# C210_0005_NINA_Module_220601.net
KiCad netlist of a schematic drawn in Altium Designer
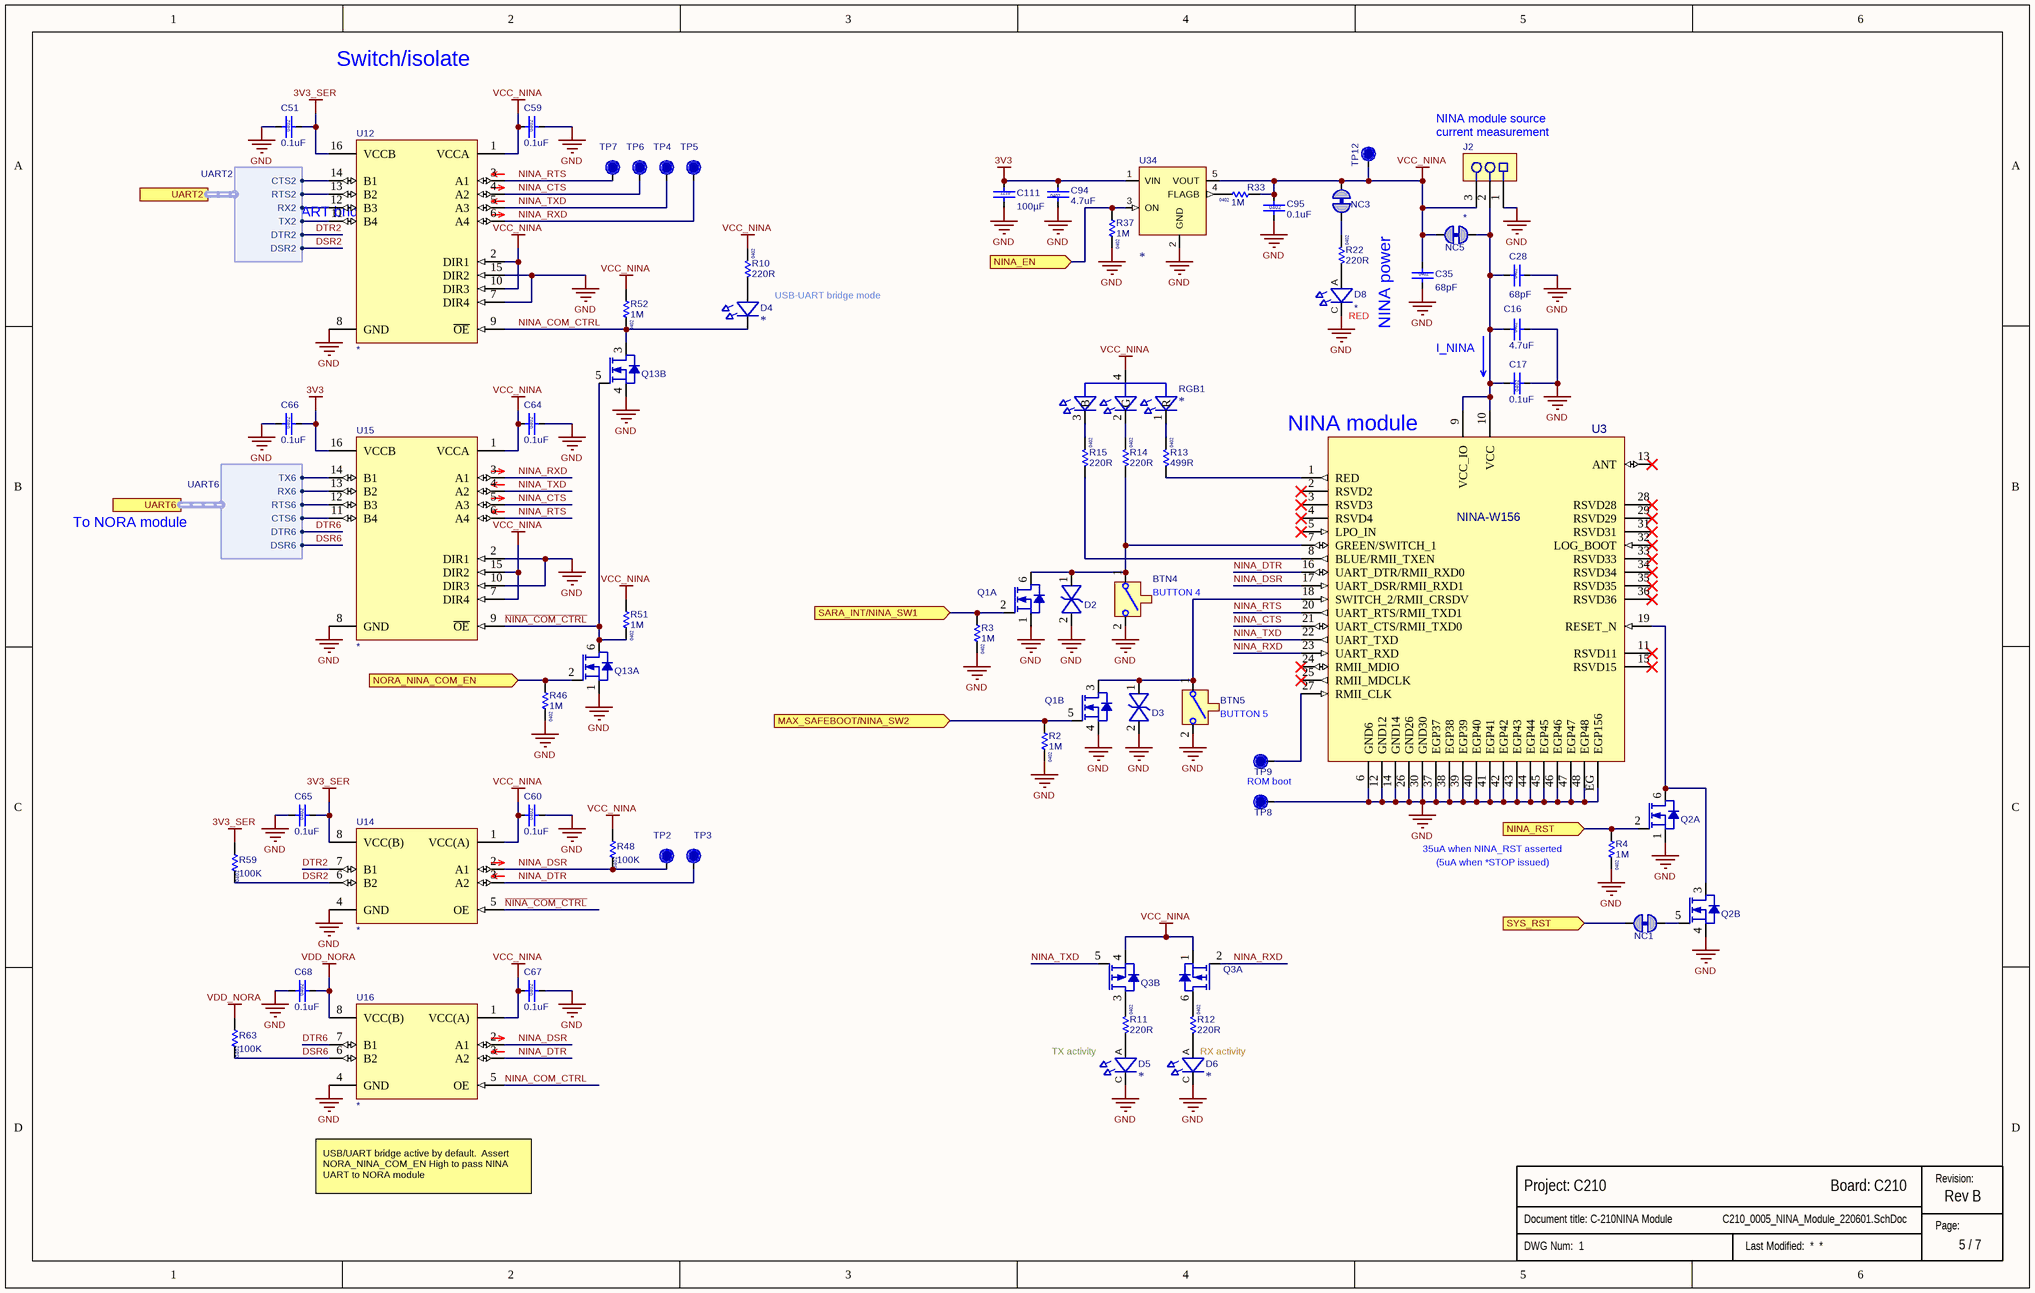
[diagram p0: C210_0005_NINA_Module_220601.SchDoc]

(export (version "E")
  (design (tool "Eeschema 10.0.6"))
  (components
    (comp (ref "BTN4")
      (value "135-00007")
      (footprint "B3U-1000P")
      (description "Button, Momentary SPST-NO, 0.05A, 12V, 3mm x 2.5mm")
      (fields (field (name "VOLTAGE") "12VDC"))
      (libsource (lib "Arena_Parts_DB_Lib") (part "SW_SPST"))
    )
    (comp (ref "BTN5")
      (value "135-00007")
      (footprint "B3U-1000P")
      (description "Button, Momentary SPST-NO, 0.05A, 12V, 3mm x 2.5mm")
      (fields (field (name "VOLTAGE") "12VDC"))
      (libsource (lib "Arena_Parts_DB_Lib") (part "SW_SPST"))
    )
    (comp (ref "C16")
      (value "4.7uF")
      (footprint "Cap 0402 HD")
      (description "Cap, Ceramic 4.7uF 10V 20% X5R 0402")
      (fields
        (field (name "SIZE") "0402")
        (field (name "PART NUMBER") "120-00020")
        (field (name "TOLERANCE") "+/- 20%")
      )
      (libsource (lib "Arena_Parts_DB_Lib") (part "Cap Chip"))
    )
    (comp (ref "C17")
      (value "0.1uF")
      (footprint "Cap 0402 HD")
      (description "Cap, Ceramic 0.1uF 10V 10% X5R 0402")
      (fields
        (field (name "SIZE") "0402")
        (field (name "PART NUMBER") "120-00016")
        (field (name "MANUFACTURER") "Murata Electronics North America")
      )
      (libsource (lib "Arena_Parts_DB_Lib") (part "Cap Chip"))
    )
    (comp (ref "C28")
      (value "68pF")
      (footprint "Cap 0402 HD")
      (description "Cap, Ceramic, 68pF, 50V, 1%, NP0, 0402")
      (fields
        (field (name "SIZE") "0402")
        (field (name "PART NUMBER") "120-00047")
        (field (name "TOLERANCE") "+/- 1%")
      )
      (libsource (lib "Arena_Parts_DB_Lib") (part "Cap Chip"))
    )
    (comp (ref "C35")
      (value "68pF")
      (footprint "Cap 0402 HD")
      (description "Cap, Ceramic, 68pF, 50V, 1%, NP0, 0402")
      (fields
        (field (name "SIZE") "0402")
        (field (name "PART NUMBER") "120-00047")
        (field (name "TOLERANCE") "+/- 1%")
      )
      (libsource (lib "Arena_Parts_DB_Lib") (part "Cap Chip"))
    )
    (comp (ref "C51")
      (value "0.1uF")
      (footprint "Cap 0402 HD")
      (description "Cap, Ceramic 0.1uF 10V 10% X5R 0402")
      (fields
        (field (name "SIZE") "0402")
        (field (name "PART NUMBER") "120-00016")
        (field (name "MANUFACTURER") "Murata Electronics North America")
      )
      (libsource (lib "Arena_Parts_DB_Lib") (part "Cap Chip"))
    )
    (comp (ref "C59")
      (value "0.1uF")
      (footprint "Cap 0402 HD")
      (description "Cap, Ceramic 0.1uF 10V 10% X5R 0402")
      (fields
        (field (name "SIZE") "0402")
        (field (name "PART NUMBER") "120-00016")
        (field (name "MANUFACTURER") "Murata Electronics North America")
      )
      (libsource (lib "Arena_Parts_DB_Lib") (part "Cap Chip"))
    )
    (comp (ref "C60")
      (value "0.1uF")
      (footprint "Cap 0402 HD")
      (description "Cap, Ceramic 0.1uF 10V 10% X5R 0402")
      (fields
        (field (name "SIZE") "0402")
        (field (name "PART NUMBER") "120-00016")
        (field (name "MANUFACTURER") "Murata Electronics North America")
      )
      (libsource (lib "Arena_Parts_DB_Lib") (part "Cap Chip"))
    )
    (comp (ref "C64")
      (value "0.1uF")
      (footprint "Cap 0402 HD")
      (description "Cap, Ceramic 0.1uF 10V 10% X5R 0402")
      (fields
        (field (name "SIZE") "0402")
        (field (name "PART NUMBER") "120-00016")
        (field (name "MANUFACTURER") "Murata Electronics North America")
      )
      (libsource (lib "Arena_Parts_DB_Lib") (part "Cap Chip"))
    )
    (comp (ref "C65")
      (value "0.1uF")
      (footprint "Cap 0402 HD")
      (description "Cap, Ceramic 0.1uF 10V 10% X5R 0402")
      (fields
        (field (name "SIZE") "0402")
        (field (name "PART NUMBER") "120-00016")
        (field (name "MANUFACTURER") "Murata Electronics North America")
      )
      (libsource (lib "Arena_Parts_DB_Lib") (part "Cap Chip"))
    )
    (comp (ref "C66")
      (value "0.1uF")
      (footprint "Cap 0402 HD")
      (description "Cap, Ceramic 0.1uF 10V 10% X5R 0402")
      (fields
        (field (name "SIZE") "0402")
        (field (name "PART NUMBER") "120-00016")
        (field (name "MANUFACTURER") "Murata Electronics North America")
      )
      (libsource (lib "Arena_Parts_DB_Lib") (part "Cap Chip"))
    )
    (comp (ref "C67")
      (value "0.1uF")
      (footprint "Cap 0402 HD")
      (description "Cap, Ceramic 0.1uF 10V 10% X5R 0402")
      (fields
        (field (name "SIZE") "0402")
        (field (name "PART NUMBER") "120-00016")
        (field (name "MANUFACTURER") "Murata Electronics North America")
      )
      (libsource (lib "Arena_Parts_DB_Lib") (part "Cap Chip"))
    )
    (comp (ref "C68")
      (value "0.1uF")
      (footprint "Cap 0402 HD")
      (description "Cap, Ceramic 0.1uF 10V 10% X5R 0402")
      (fields
        (field (name "SIZE") "0402")
        (field (name "PART NUMBER") "120-00016")
        (field (name "MANUFACTURER") "Murata Electronics North America")
      )
      (libsource (lib "Arena_Parts_DB_Lib") (part "Cap Chip"))
    )
    (comp (ref "C94")
      (value "4.7uF")
      (footprint "Cap 0402 HD")
      (description "Cap, Ceramic 4.7uF 10V 20% X5R 0402")
      (fields
        (field (name "SIZE") "0402")
        (field (name "PART NUMBER") "120-00020")
        (field (name "TOLERANCE") "+/- 20%")
      )
      (libsource (lib "Arena_Parts_DB_Lib") (part "Cap Chip"))
    )
    (comp (ref "C95")
      (value "0.1uF")
      (footprint "Cap 0402 HD")
      (description "Cap, Ceramic 0.1uF 10V 10% X5R 0402")
      (fields
        (field (name "SIZE") "0402")
        (field (name "PART NUMBER") "120-00016")
        (field (name "MANUFACTURER") "Murata Electronics North America")
      )
      (libsource (lib "Arena_Parts_DB_Lib") (part "Cap Chip"))
    )
    (comp (ref "C111")
      (value "100µF")
      (footprint "Cap 1210")
      (description "100µF ±20% 10V Ceramic Capacitor X5R 1210 (3225 Metric)")
      (fields
        (field (name "SIZE") "1210")
        (field (name "PART NUMBER") "120-00223")
        (field (name "TOLERANCE") "+/- 20%")
      )
      (libsource (lib "Arena_Parts_DB_Lib") (part "Cap Chip"))
    )
    (comp (ref "D2")
      (value "110-00041")
      (footprint "SOD-523_ALT")
      (description "Diode TVS 5VWM BiDIR SOD523")
      (fields (field (name "VOLTAGE") "5VWM"))
      (libsource (lib "Arena_Parts_DB_Lib") (part "Diode_TVS"))
    )
    (comp (ref "D3")
      (value "110-00041")
      (footprint "SOD-523_ALT")
      (description "Diode TVS 5VWM BiDIR SOD523")
      (fields (field (name "VOLTAGE") "5VWM"))
      (libsource (lib "Arena_Parts_DB_Lib") (part "Diode_TVS"))
    )
    (comp (ref "D4")
      (value "115-00023")
      (footprint "LED-0603")
      (description "LED BLUE DIFFUSED 0603 SMD")
      (fields (field (name "COLOR") "*") (field (name "VOLTAGE") "None"))
      (libsource (lib "Arena_Parts_DB_Lib") (part "LED_BASE"))
    )
    (comp (ref "D5")
      (value "115-00019")
      (footprint "LTST-C190KGKT")
      (description "DIODE, LED, SMT, GREEN, CLEAR LENS, 2.0V 20mA, 0603")
      (fields (field (name "VOLTAGE") "2.0V") (field (name "COLOR") "*"))
      (libsource (lib "LTST-C190KGKT") (part "LTST-C190KGKT"))
    )
    (comp (ref "D6")
      (value "LTST-C190YKT")
      (footprint "LTST-C190YKT")
      (description "DIODE, LED, SMT, YELLOW, CLEAR LENS, 2.1V 10mA, 0603")
      (fields (field (name "VOLTAGE") "2.1V") (field (name "COLOR") "*"))
      (libsource (lib "LTST-C190YKT") (part "LTST-C190YKT"))
    )
    (comp (ref "D8")
      (value "LTST-C190EKT")
      (footprint "LTST-C190EKT")
      (description "DIODE, LED, SMT, Red, CLEAR LENS, 2.0V 10mA, 0603")
      (fields (field (name "VOLTAGE") "2.0V") (field (name "COLOR") "*"))
      (libsource (lib "LTST-C190EKT") (part "LTST-C190EKT"))
    )
    (comp (ref "J2")
      (value "130-00105")
      (footprint "HDR-0.1P-3Pin-1Row-SMT")
      (description "Header, 0.100\" Pitch, 3 Pin, Vertical SMT, Black")
      (fields (field (name "MANUFACTURER P/N") "*") (field (name "VOLTAGE") "None"))
      (libsource (lib "Arena_Parts_DB_Lib") (part "CON-3Pin_1Row"))
    )
    (comp (ref "NC1")
      (value "Solderbridge-ShortDNP")
      (footprint "Solderbridge-Short")
      (description "Solderbridge-Short")
      (fields (field (name "ADDED BY") "Paul B"))
      (libsource (lib "") (part "Solderbridge-Short_1"))
    )
    (comp (ref "NC3")
      (value "Solderbridge-ShortDNP")
      (footprint "Solderbridge-Short")
      (description "Solderbridge-Short")
      (fields (field (name "ADDED BY") "Paul B"))
      (libsource (lib "PCB_Misc") (part "Solderbridge-Short"))
    )
    (comp (ref "NC5")
      (value "Solderbridge-ShortDNP")
      (footprint "Solderbridge-Short")
      (description "Solderbridge-Short")
      (fields (field (name "ADDED BY") "Paul B"))
      (libsource (lib "") (part "Solderbridge-Short_1"))
    )
    (comp (ref "Q1")
      (value "140-00016")
      (footprint "SOT-563")
      (description "MOSFET 2N-CH 20V 0.8A, SOT-563")
      (fields (field (name "VOLTAGE") "20V"))
      (libsource (lib "Arena_Parts_DB_Lib") (part "MOSFET-N-Dual"))
    )
    (comp (ref "Q2")
      (value "140-00016")
      (footprint "SOT-563")
      (description "MOSFET 2N-CH 20V 0.8A, SOT-563")
      (fields (field (name "VOLTAGE") "20V"))
      (libsource (lib "Arena_Parts_DB_Lib") (part "MOSFET-N-Dual"))
    )
    (comp (ref "Q3")
      (value "FDY2000PZ")
      (footprint "FDY2000PZ")
      (description "MOSFET DUAL P-CH 20V SOT-563, -350mA")
      (fields (field (name "VOLTAGE") "20V"))
      (libsource (lib "FDY2000PZ") (part "MOSFET-Dual-P_Chan"))
    )
    (comp (ref "Q13")
      (value "140-00016")
      (footprint "SOT-563")
      (description "MOSFET 2N-CH 20V 0.8A, SOT-563")
      (fields (field (name "VOLTAGE") "20V"))
      (libsource (lib "Arena_Parts_DB_Lib") (part "MOSFET-N-Dual"))
    )
    (comp (ref "R2")
      (value "1M")
      (footprint "RES 0402 HD")
      (description "Resistor 1M ohm 1%, 1/16W, 0402")
      (fields
        (field (name "SIZE") "0402")
        (field (name "PART NUMBER") "180-00054")
        (field (name "POWER") "1/16W")
      )
      (libsource (lib "Arena_Parts_DB_Lib") (part "Res sm"))
    )
    (comp (ref "R3")
      (value "1M")
      (footprint "RES 0402 HD")
      (description "Resistor 1M ohm 1%, 1/16W, 0402")
      (fields
        (field (name "SIZE") "0402")
        (field (name "PART NUMBER") "180-00054")
        (field (name "POWER") "1/16W")
      )
      (libsource (lib "Arena_Parts_DB_Lib") (part "Res sm"))
    )
    (comp (ref "R4")
      (value "1M")
      (footprint "RES 0402 HD")
      (description "Resistor 1M ohm 1%, 1/16W, 0402")
      (fields
        (field (name "SIZE") "0402")
        (field (name "PART NUMBER") "180-00054")
        (field (name "POWER") "1/16W")
      )
      (libsource (lib "Arena_Parts_DB_Lib") (part "Res sm"))
    )
    (comp (ref "R10")
      (value "220R")
      (footprint "RES 0402 HD")
      (description "Resistor, 220ohm, 5%, 1/16W, 0402.")
      (fields
        (field (name "SIZE") "0402")
        (field (name "PART NUMBER") "180-00098")
        (field (name "MANUFACTURER") "Panasonic Electronic Components")
      )
      (libsource (lib "Arena_Parts_DB_Lib") (part "Res sm"))
    )
    (comp (ref "R11")
      (value "220R")
      (footprint "RES 0402 HD")
      (description "Resistor, 220ohm, 5%, 1/16W, 0402.")
      (fields
        (field (name "SIZE") "0402")
        (field (name "PART NUMBER") "180-00098")
        (field (name "MANUFACTURER") "Panasonic Electronic Components")
      )
      (libsource (lib "Arena_Parts_DB_Lib") (part "Res sm"))
    )
    (comp (ref "R12")
      (value "220R")
      (footprint "RES 0402 HD")
      (description "Resistor, 220ohm, 5%, 1/16W, 0402.")
      (fields
        (field (name "SIZE") "0402")
        (field (name "PART NUMBER") "180-00098")
        (field (name "MANUFACTURER") "Panasonic Electronic Components")
      )
      (libsource (lib "Arena_Parts_DB_Lib") (part "Res sm"))
    )
    (comp (ref "R13")
      (value "499R")
      (footprint "RES 0402 HD")
      (description "Resistor, 499ohm, 1%, 1/16W, 0402")
      (fields
        (field (name "SIZE") "0402")
        (field (name "PART NUMBER") "180-00031")
        (field (name "MANUFACTURER") "Rohm Semiconductor")
      )
      (libsource (lib "Arena_Parts_DB_Lib") (part "Res sm"))
    )
    (comp (ref "R14")
      (value "220R")
      (footprint "RES 0402 HD")
      (description "Resistor, 220ohm, 5%, 1/16W, 0402.")
      (fields
        (field (name "SIZE") "0402")
        (field (name "PART NUMBER") "180-00098")
        (field (name "MANUFACTURER") "Panasonic Electronic Components")
      )
      (libsource (lib "Arena_Parts_DB_Lib") (part "Res sm"))
    )
    (comp (ref "R15")
      (value "220R")
      (footprint "RES 0402 HD")
      (description "Resistor, 220ohm, 5%, 1/16W, 0402.")
      (fields
        (field (name "SIZE") "0402")
        (field (name "PART NUMBER") "180-00098")
        (field (name "MANUFACTURER") "Panasonic Electronic Components")
      )
      (libsource (lib "Arena_Parts_DB_Lib") (part "Res sm"))
    )
    (comp (ref "R22")
      (value "220R")
      (footprint "RES 0402 HD")
      (description "Resistor, 220ohm, 5%, 1/16W, 0402.")
      (fields
        (field (name "SIZE") "0402")
        (field (name "PART NUMBER") "180-00098")
        (field (name "MANUFACTURER") "Panasonic Electronic Components")
      )
      (libsource (lib "Arena_Parts_DB_Lib") (part "Res sm"))
    )
    (comp (ref "R33")
      (value "1M")
      (footprint "RES 0402 HD")
      (description "Resistor 1M ohm 1%, 1/16W, 0402")
      (fields
        (field (name "SIZE") "0402")
        (field (name "PART NUMBER") "180-00054")
        (field (name "POWER") "1/16W")
      )
      (libsource (lib "Arena_Parts_DB_Lib") (part "Res sm"))
    )
    (comp (ref "R37")
      (value "1M")
      (footprint "RES 0402 HD")
      (description "Resistor 1M ohm 1%, 1/16W, 0402")
      (fields
        (field (name "SIZE") "0402")
        (field (name "PART NUMBER") "180-00054")
        (field (name "POWER") "1/16W")
      )
      (libsource (lib "Arena_Parts_DB_Lib") (part "Res sm"))
    )
    (comp (ref "R46")
      (value "1M")
      (footprint "RES 0402 HD")
      (description "Resistor 1M ohm 1%, 1/16W, 0402")
      (fields
        (field (name "SIZE") "0402")
        (field (name "PART NUMBER") "180-00054")
        (field (name "POWER") "1/16W")
      )
      (libsource (lib "Arena_Parts_DB_Lib") (part "Res sm"))
    )
    (comp (ref "R48")
      (value "100K")
      (footprint "RES 0402 HD")
      (description "Resistor 100K ohm 1% 1/16W, 0402")
      (fields
        (field (name "SIZE") "0402")
        (field (name "PART NUMBER") "180-00093")
        (field (name "POWER") "1/16W")
      )
      (libsource (lib "Arena_Parts_DB_Lib") (part "Res sm"))
    )
    (comp (ref "R51")
      (value "1M")
      (footprint "RES 0402 HD")
      (description "Resistor 1M ohm 1%, 1/16W, 0402")
      (fields
        (field (name "SIZE") "0402")
        (field (name "PART NUMBER") "180-00054")
        (field (name "POWER") "1/16W")
      )
      (libsource (lib "Arena_Parts_DB_Lib") (part "Res sm"))
    )
    (comp (ref "R52")
      (value "1M")
      (footprint "RES 0402 HD")
      (description "Resistor 1M ohm 1%, 1/16W, 0402")
      (fields
        (field (name "SIZE") "0402")
        (field (name "PART NUMBER") "180-00054")
        (field (name "POWER") "1/16W")
      )
      (libsource (lib "Arena_Parts_DB_Lib") (part "Res sm"))
    )
    (comp (ref "R59")
      (value "100K")
      (footprint "RES 0402 HD")
      (description "Resistor 100K ohm 1% 1/16W, 0402")
      (fields
        (field (name "SIZE") "0402")
        (field (name "PART NUMBER") "180-00093")
        (field (name "POWER") "1/16W")
      )
      (libsource (lib "Arena_Parts_DB_Lib") (part "Res sm"))
    )
    (comp (ref "R63")
      (value "100K")
      (footprint "RES 0402 HD")
      (description "Resistor 100K ohm 1% 1/16W, 0402")
      (fields
        (field (name "SIZE") "0402")
        (field (name "PART NUMBER") "180-00093")
        (field (name "POWER") "1/16W")
      )
      (libsource (lib "Arena_Parts_DB_Lib") (part "Res sm"))
    )
    (comp (ref "RGB1")
      (value "115-00026")
      (footprint "LED_1616")
      (description "LED RGB SMT 0606")
      (fields (field (name "COLOR") "*") (field (name "VOLTAGE") "None"))
      (libsource (lib "Arena_Parts_DB_Lib") (part "LED_RGB_CA_4"))
    )
    (comp (ref "TP2")
      (value "TP")
      (footprint "TP12R")
      (description "Testpoint, Round 1.0mm Dia")
      (fields
        (field (name "PART NUMBER") "TP10R")
        (field (name "ADDED BY") "Jeremy D")
        (field (name "CHECKED BY") "Paul B")
      )
      (libsource (lib "PCB_Misc") (part "TP_R"))
    )
    (comp (ref "TP3")
      (value "TP")
      (footprint "TP12R")
      (description "Testpoint, Round 1.0mm Dia")
      (fields
        (field (name "PART NUMBER") "TP10R")
        (field (name "ADDED BY") "Jeremy D")
        (field (name "CHECKED BY") "Paul B")
      )
      (libsource (lib "PCB_Misc") (part "TP_R"))
    )
    (comp (ref "TP4")
      (value "TP")
      (footprint "TP12R")
      (description "Testpoint, Round 1.0mm Dia")
      (fields
        (field (name "PART NUMBER") "TP10R")
        (field (name "ADDED BY") "Jeremy D")
        (field (name "CHECKED BY") "Paul B")
      )
      (libsource (lib "PCB_Misc") (part "TP_R"))
    )
    (comp (ref "TP5")
      (value "TP")
      (footprint "TP12R")
      (description "Testpoint, Round 1.0mm Dia")
      (fields
        (field (name "PART NUMBER") "TP10R")
        (field (name "ADDED BY") "Jeremy D")
        (field (name "CHECKED BY") "Paul B")
      )
      (libsource (lib "PCB_Misc") (part "TP_R"))
    )
    (comp (ref "TP6")
      (value "TP")
      (footprint "TP12R")
      (description "Testpoint, Round 1.0mm Dia")
      (fields
        (field (name "PART NUMBER") "TP10R")
        (field (name "ADDED BY") "Jeremy D")
        (field (name "CHECKED BY") "Paul B")
      )
      (libsource (lib "PCB_Misc") (part "TP_R"))
    )
    (comp (ref "TP7")
      (value "TP")
      (footprint "TP12R")
      (description "Testpoint, Round 1.0mm Dia")
      (fields
        (field (name "PART NUMBER") "TP10R")
        (field (name "ADDED BY") "Jeremy D")
        (field (name "CHECKED BY") "Paul B")
      )
      (libsource (lib "PCB_Misc") (part "TP_R"))
    )
    (comp (ref "TP8")
      (value "TP")
      (footprint "TP12R")
      (description "Testpoint, Round 1.0mm Dia")
      (fields
        (field (name "PART NUMBER") "TP10R")
        (field (name "ADDED BY") "Jeremy D")
        (field (name "CHECKED BY") "Paul B")
      )
      (libsource (lib "PCB_Misc") (part "TP_R"))
    )
    (comp (ref "TP9")
      (value "TP")
      (footprint "TP12R")
      (description "Testpoint, Round 1.0mm Dia")
      (fields
        (field (name "PART NUMBER") "TP10R")
        (field (name "ADDED BY") "Jeremy D")
        (field (name "CHECKED BY") "Paul B")
      )
      (libsource (lib "PCB_Misc") (part "TP_R"))
    )
    (comp (ref "TP12")
      (value "TP")
      (footprint "TP12R")
      (description "Testpoint, Round 1.0mm Dia")
      (fields
        (field (name "PART NUMBER") "TP10R")
        (field (name "ADDED BY") "Jeremy D")
        (field (name "CHECKED BY") "Paul B")
      )
      (libsource (lib "PCB_Misc") (part "TP_R"))
    )
    (comp (ref "U3")
      (value "NINA-W156")
      (footprint "NINA_LGA48R_1400X1000X223_PCB")
      (description "u-blox NINA-W156 WiFi, Bluetooth dual-mode module")
      (fields (field (name "MANUFACTURER") "u-blox"))
      (libsource (lib "ubloxLib") (part "NINA-W156"))
    )
    (comp (ref "U12")
      (value "225-00011")
      (footprint "QFN0.5P2x6-16Pin_W-Pad")
      (description "Voltage Level Translator Bidirectional 1 Circuit 4 Channel 380Mbps 16-DHVQFN (2.5x3.5)")
      (fields (field (name "MANUFACTURER P/N") "*") (field (name "VOLTAGE") "3.6V"))
      (libsource (lib "Arena_Parts_DB_Lib") (part "74AVC4TD245"))
    )
    (comp (ref "U14")
      (value "225-00008")
      (footprint "QFN0.4P3x1-8Pin")
      (description "IC Dual Translating Transceiver, 8XQFN")
      (fields (field (name "MANUFACTURER P/N") "*") (field (name "VOLTAGE") "5.5V"))
      (libsource (lib "Arena_Parts_DB_Lib") (part "NTSX2102GU8H"))
    )
    (comp (ref "U15")
      (value "225-00011")
      (footprint "QFN0.5P2x6-16Pin_W-Pad")
      (description "Voltage Level Translator Bidirectional 1 Circuit 4 Channel 380Mbps 16-DHVQFN (2.5x3.5)")
      (fields (field (name "MANUFACTURER P/N") "*") (field (name "VOLTAGE") "3.6V"))
      (libsource (lib "Arena_Parts_DB_Lib") (part "74AVC4TD245"))
    )
    (comp (ref "U16")
      (value "225-00008")
      (footprint "QFN0.4P3x1-8Pin")
      (description "IC Dual Translating Transceiver, 8XQFN")
      (fields (field (name "MANUFACTURER P/N") "*") (field (name "VOLTAGE") "5.5V"))
      (libsource (lib "Arena_Parts_DB_Lib") (part "NTSX2102GU8H"))
    )
    (comp (ref "U34")
      (value "~")
      (footprint "SOT-23-5_2")
      (description "Load Switch, 400mA, 1.8-5.5V, Active High Enable, SOT-23-5")
      (fields (field (name "VOLTAGE") "5.5V") (field (name "MANUFACTURER P/N") "*"))
      (libsource (lib "FPF2104") (part "FPF2104"))
    )
  )
  (nets
    (net (code "3") (name "/CTS2") (class "Default")
      (node (ref "U12") (pin "14") (pinfunction "B1_14") (pintype "bidirectional"))
    )
    (net (code "4") (name "/CTS6") (class "Default")
      (node (ref "U15") (pin "11") (pinfunction "B4_11") (pintype "bidirectional"))
    )
    (net (code "5") (name "/DSR2") (class "Default")
      (node (ref "R59") (pin "2") (pinfunction "2_2") (pintype "passive"))
      (node (ref "U14") (pin "6") (pinfunction "B2_6") (pintype "bidirectional"))
    )
    (net (code "6") (name "/DSR6") (class "Default")
      (node (ref "R63") (pin "2") (pinfunction "2_2") (pintype "passive"))
      (node (ref "U16") (pin "6") (pinfunction "B2_6") (pintype "bidirectional"))
    )
    (net (code "7") (name "/DTR2") (class "Default")
      (node (ref "U14") (pin "7") (pinfunction "B1_7") (pintype "bidirectional"))
    )
    (net (code "8") (name "/DTR6") (class "Default")
      (node (ref "U16") (pin "7") (pinfunction "B1_7") (pintype "bidirectional"))
    )
    (net (code "9") (name "/MAX_SAFEBOOT{slash}NINA_SW2") (class "Default")
      (node (ref "Q1") (pin "5") (pinfunction "G2_5") (pintype "passive"))
      (node (ref "R2") (pin "1") (pinfunction "1_1") (pintype "passive"))
    )
    (net (code "10") (name "/NINA_COM_CTRL") (class "Default")
      (node (ref "D4") (pin "1") (pinfunction "C_1") (pintype "passive"))
      (node (ref "Q13") (pin "3") (pinfunction "D2_3") (pintype "passive"))
      (node (ref "R52") (pin "2") (pinfunction "2_2") (pintype "passive"))
      (node (ref "U12") (pin "9") (pinfunction "~{OE}_9") (pintype "input"))
      (node (ref "U16") (pin "5") (pinfunction "OE_5") (pintype "input"))
    )
    (net (code "11") (name "/NINA_CTS") (class "Default")
      (node (ref "TP6") (pin "1") (pintype "passive"))
      (node (ref "U12") (pin "4") (pinfunction "A2_4") (pintype "bidirectional"))
      (node (ref "U15") (pin "5") (pinfunction "A3_5") (pintype "bidirectional"))
      (node (ref "U3") (pin "21") (pinfunction "UART_CTS/RMII_TXD0_21") (pintype "bidirectional"))
    )
    (net (code "12") (name "/NINA_DSR") (class "Default")
      (node (ref "R48") (pin "2") (pinfunction "2_2") (pintype "passive"))
      (node (ref "TP2") (pin "1") (pintype "passive"))
      (node (ref "U14") (pin "2") (pinfunction "A1_2") (pintype "bidirectional"))
      (node (ref "U16") (pin "2") (pinfunction "A1_2") (pintype "bidirectional"))
      (node (ref "U3") (pin "17") (pinfunction "UART_DSR/RMII_RXD1_17") (pintype "input"))
    )
    (net (code "13") (name "/NINA_DTR") (class "Default")
      (node (ref "TP3") (pin "1") (pintype "passive"))
      (node (ref "U14") (pin "3") (pinfunction "A2_3") (pintype "bidirectional"))
      (node (ref "U16") (pin "3") (pinfunction "A2_3") (pintype "bidirectional"))
      (node (ref "U3") (pin "16") (pinfunction "UART_DTR/RMII_RXD0_16") (pintype "bidirectional"))
    )
    (net (code "14") (name "/NINA_EN") (class "Default")
      (node (ref "R37") (pin "1") (pinfunction "1_1") (pintype "passive"))
      (node (ref "U34") (pin "3") (pinfunction "ON_3") (pintype "input"))
    )
    (net (code "15") (name "/NINA_RST") (class "Default")
      (node (ref "Q2") (pin "2") (pinfunction "G1_2") (pintype "passive"))
      (node (ref "R4") (pin "1") (pinfunction "1_1") (pintype "passive"))
    )
    (net (code "16") (name "/NINA_RTS") (class "Default")
      (node (ref "TP7") (pin "1") (pintype "passive"))
      (node (ref "U12") (pin "3") (pinfunction "A1_3") (pintype "bidirectional"))
      (node (ref "U15") (pin "6") (pinfunction "A4_6") (pintype "bidirectional"))
      (node (ref "U3") (pin "20") (pinfunction "UART_RTS/RMII_TXD1_20") (pintype "output"))
    )
    (net (code "17") (name "/NINA_RXD") (class "Default")
      (node (ref "Q3") (pin "2") (pinfunction "G1_2") (pintype "passive"))
      (node (ref "TP5") (pin "1") (pintype "passive"))
      (node (ref "U12") (pin "6") (pinfunction "A4_6") (pintype "bidirectional"))
      (node (ref "U15") (pin "3") (pinfunction "A1_3") (pintype "bidirectional"))
      (node (ref "U3") (pin "23") (pinfunction "UART_RXD_23") (pintype "input"))
    )
    (net (code "18") (name "/NINA_TXD") (class "Default")
      (node (ref "Q3") (pin "5") (pinfunction "G2_5") (pintype "passive"))
      (node (ref "TP4") (pin "1") (pintype "passive"))
      (node (ref "U12") (pin "5") (pinfunction "A3_5") (pintype "bidirectional"))
      (node (ref "U15") (pin "4") (pinfunction "A2_4") (pintype "bidirectional"))
      (node (ref "U3") (pin "22") (pinfunction "UART_TXD_22") (pintype "output"))
    )
    (net (code "19") (name "/NORA_NINA_COM_EN") (class "Default")
      (node (ref "Q13") (pin "2") (pinfunction "G1_2") (pintype "passive"))
      (node (ref "R46") (pin "1") (pinfunction "1_1") (pintype "passive"))
    )
    (net (code "20") (name "/RTS2") (class "Default")
      (node (ref "U12") (pin "13") (pinfunction "B2_13") (pintype "bidirectional"))
    )
    (net (code "21") (name "/RTS6") (class "Default")
      (node (ref "U15") (pin "12") (pinfunction "B3_12") (pintype "bidirectional"))
    )
    (net (code "22") (name "/RX2") (class "Default")
      (node (ref "U12") (pin "12") (pinfunction "B3_12") (pintype "bidirectional"))
    )
    (net (code "23") (name "/RX6") (class "Default")
      (node (ref "U15") (pin "13") (pinfunction "B2_13") (pintype "bidirectional"))
    )
    (net (code "24") (name "/SARA_INT{slash}NINA_SW1") (class "Default")
      (node (ref "Q1") (pin "2") (pinfunction "G1_2") (pintype "passive"))
      (node (ref "R3") (pin "1") (pinfunction "1_1") (pintype "passive"))
    )
    (net (code "25") (name "/SYS_RST") (class "Default")
      (node (ref "NC1") (pin "2") (pinfunction "2_2") (pintype "passive"))
    )
    (net (code "26") (name "/TX2") (class "Default")
      (node (ref "U12") (pin "11") (pinfunction "B4_11") (pintype "bidirectional"))
    )
    (net (code "27") (name "/TX6") (class "Default")
      (node (ref "U15") (pin "14") (pinfunction "B1_14") (pintype "bidirectional"))
    )
    (net (code "30") (name "/~{NINA_COM_CTRL}") (class "Default")
      (node (ref "Q13") (pin "5") (pinfunction "G2_5") (pintype "passive"))
      (node (ref "Q13") (pin "6") (pinfunction "D1_6") (pintype "passive"))
      (node (ref "R51") (pin "2") (pinfunction "2_2") (pintype "passive"))
      (node (ref "U14") (pin "5") (pinfunction "OE_5") (pintype "input"))
      (node (ref "U15") (pin "9") (pinfunction "~{OE}_9") (pintype "input"))
    )
    (net (code "31") (name "3V3") (class "Default")
      (node (ref "C111") (pin "1") (pinfunction "1_1") (pintype "passive"))
      (node (ref "C66") (pin "2") (pinfunction "2_2") (pintype "passive"))
      (node (ref "C94") (pin "2") (pinfunction "2_2") (pintype "passive"))
      (node (ref "U15") (pin "16") (pinfunction "VCCB_16") (pintype "power_in"))
      (node (ref "U34") (pin "1") (pinfunction "VIN_1") (pintype "power_in"))
    )
    (net (code "32") (name "3V3_SER") (class "Default")
      (node (ref "C51") (pin "2") (pinfunction "2_2") (pintype "passive"))
      (node (ref "C65") (pin "2") (pinfunction "2_2") (pintype "passive"))
      (node (ref "R59") (pin "1") (pinfunction "1_1") (pintype "passive"))
      (node (ref "U12") (pin "16") (pinfunction "VCCB_16") (pintype "power_in"))
      (node (ref "U14") (pin "8") (pinfunction "VCC(B)_8") (pintype "power_in"))
    )
    (net (code "33") (name "GND") (class "Default")
      (node (ref "BTN4") (pin "2") (pinfunction "2_2") (pintype "passive"))
      (node (ref "BTN5") (pin "2") (pinfunction "2_2") (pintype "passive"))
      (node (ref "C111") (pin "2") (pinfunction "2_2") (pintype "passive"))
      (node (ref "C16") (pin "2") (pinfunction "2_2") (pintype "passive"))
      (node (ref "C17") (pin "1") (pinfunction "1_1") (pintype "passive"))
      (node (ref "C28") (pin "2") (pinfunction "2_2") (pintype "passive"))
      (node (ref "C35") (pin "2") (pinfunction "2_2") (pintype "passive"))
      (node (ref "C51") (pin "1") (pinfunction "1_1") (pintype "passive"))
      (node (ref "C59") (pin "2") (pinfunction "2_2") (pintype "passive"))
      (node (ref "C60") (pin "2") (pinfunction "2_2") (pintype "passive"))
      (node (ref "C64") (pin "2") (pinfunction "2_2") (pintype "passive"))
      (node (ref "C65") (pin "1") (pinfunction "1_1") (pintype "passive"))
      (node (ref "C66") (pin "1") (pinfunction "1_1") (pintype "passive"))
      (node (ref "C67") (pin "2") (pinfunction "2_2") (pintype "passive"))
      (node (ref "C68") (pin "1") (pinfunction "1_1") (pintype "passive"))
      (node (ref "C94") (pin "1") (pinfunction "1_1") (pintype "passive"))
      (node (ref "C95") (pin "2") (pinfunction "2_2") (pintype "passive"))
      (node (ref "D2") (pin "2") (pintype "passive"))
      (node (ref "D3") (pin "2") (pintype "passive"))
      (node (ref "D5") (pin "C") (pinfunction "Cathode_C") (pintype "passive"))
      (node (ref "D6") (pin "C") (pinfunction "Cathode_C") (pintype "passive"))
      (node (ref "D8") (pin "C") (pinfunction "Cathode_C") (pintype "passive"))
      (node (ref "J2") (pin "1") (pinfunction "1_1") (pintype "passive"))
      (node (ref "Q1") (pin "1") (pinfunction "S1_1") (pintype "passive"))
      (node (ref "Q1") (pin "4") (pinfunction "S2_4") (pintype "passive"))
      (node (ref "Q13") (pin "1") (pinfunction "S1_1") (pintype "passive"))
      (node (ref "Q13") (pin "4") (pinfunction "S2_4") (pintype "passive"))
      (node (ref "Q2") (pin "1") (pinfunction "S1_1") (pintype "passive"))
      (node (ref "Q2") (pin "4") (pinfunction "S2_4") (pintype "passive"))
      (node (ref "R2") (pin "2") (pinfunction "2_2") (pintype "passive"))
      (node (ref "R3") (pin "2") (pinfunction "2_2") (pintype "passive"))
      (node (ref "R37") (pin "2") (pinfunction "2_2") (pintype "passive"))
      (node (ref "R4") (pin "2") (pinfunction "2_2") (pintype "passive"))
      (node (ref "R46") (pin "2") (pinfunction "2_2") (pintype "passive"))
      (node (ref "TP8") (pin "1") (pintype "passive"))
      (node (ref "U12") (pin "15") (pinfunction "DIR2_15") (pintype "input"))
      (node (ref "U12") (pin "7") (pinfunction "DIR4_7") (pintype "input"))
      (node (ref "U12") (pin "8") (pinfunction "GND_8") (pintype "power_in"))
      (node (ref "U14") (pin "4") (pinfunction "GND_4") (pintype "power_in"))
      (node (ref "U15") (pin "10") (pinfunction "DIR3_10") (pintype "input"))
      (node (ref "U15") (pin "2") (pinfunction "DIR1_2") (pintype "input"))
      (node (ref "U15") (pin "8") (pinfunction "GND_8") (pintype "power_in"))
      (node (ref "U16") (pin "4") (pinfunction "GND_4") (pintype "power_in"))
      (node (ref "U3") (pin "12") (pinfunction "GND12_12") (pintype "power_in"))
      (node (ref "U3") (pin "14") (pinfunction "GND14_14") (pintype "power_in"))
      (node (ref "U3") (pin "26") (pinfunction "GND26_26") (pintype "power_in"))
      (node (ref "U3") (pin "30") (pinfunction "GND30_30") (pintype "power_in"))
      (node (ref "U3") (pin "37") (pinfunction "EGP37_37") (pintype "power_in"))
      (node (ref "U3") (pin "38") (pinfunction "EGP38_38") (pintype "power_in"))
      (node (ref "U3") (pin "39") (pinfunction "EGP39_39") (pintype "power_in"))
      (node (ref "U3") (pin "40") (pinfunction "EGP40_40") (pintype "power_in"))
      (node (ref "U3") (pin "41") (pinfunction "EGP41_41") (pintype "power_in"))
      (node (ref "U3") (pin "42") (pinfunction "EGP42_42") (pintype "power_in"))
      (node (ref "U3") (pin "43") (pinfunction "EGP43_43") (pintype "power_in"))
      (node (ref "U3") (pin "44") (pinfunction "EGP44_44") (pintype "power_in"))
      (node (ref "U3") (pin "45") (pinfunction "EGP45_45") (pintype "power_in"))
      (node (ref "U3") (pin "46") (pinfunction "EGP46_46") (pintype "power_in"))
      (node (ref "U3") (pin "47") (pinfunction "EGP47_47") (pintype "power_in"))
      (node (ref "U3") (pin "48") (pinfunction "EGP48_48") (pintype "power_in"))
      (node (ref "U3") (pin "6") (pinfunction "GND6_6") (pintype "power_in"))
      (node (ref "U3") (pin "EG") (pinfunction "EGP156_EG") (pintype "power_in"))
      (node (ref "U34") (pin "2") (pinfunction "GND_2") (pintype "power_in"))
    )
    (net (code "34") (name "Net-(D4-A)") (class "Default")
      (node (ref "D4") (pin "2") (pinfunction "A_2") (pintype "passive"))
      (node (ref "R10") (pin "1") (pinfunction "1_1") (pintype "passive"))
    )
    (net (code "35") (name "Net-(D5-Anode)") (class "Default")
      (node (ref "D5") (pin "A") (pinfunction "Anode_A") (pintype "passive"))
      (node (ref "R11") (pin "1") (pinfunction "1_1") (pintype "passive"))
    )
    (net (code "36") (name "Net-(D6-Anode)") (class "Default")
      (node (ref "D6") (pin "A") (pinfunction "Anode_A") (pintype "passive"))
      (node (ref "R12") (pin "1") (pinfunction "1_1") (pintype "passive"))
    )
    (net (code "37") (name "Net-(D8-Anode)") (class "Default")
      (node (ref "D8") (pin "A") (pinfunction "Anode_A") (pintype "passive"))
      (node (ref "R22") (pin "1") (pinfunction "1_1") (pintype "passive"))
    )
    (net (code "38") (name "Net-(NC3-Pad2)") (class "Default")
      (node (ref "NC3") (pin "2") (pinfunction "2_2") (pintype "passive"))
      (node (ref "R22") (pin "2") (pinfunction "2_2") (pintype "passive"))
    )
    (net (code "39") (name "Net-(Q1A-D1)") (class "Default")
      (node (ref "BTN4") (pin "1") (pinfunction "1_1") (pintype "passive"))
      (node (ref "D2") (pin "1") (pintype "passive"))
      (node (ref "Q1") (pin "6") (pinfunction "D1_6") (pintype "passive"))
      (node (ref "R14") (pin "1") (pinfunction "1_1") (pintype "passive"))
      (node (ref "U3") (pin "7") (pinfunction "GREEN/SWITCH_1_7") (pintype "bidirectional"))
    )
    (net (code "40") (name "Net-(Q1B-D2)") (class "Default")
      (node (ref "BTN5") (pin "1") (pinfunction "1_1") (pintype "passive"))
      (node (ref "D3") (pin "1") (pintype "passive"))
      (node (ref "Q1") (pin "3") (pinfunction "D2_3") (pintype "passive"))
      (node (ref "U3") (pin "18") (pinfunction "SWITCH_2/RMII_CRSDV_18") (pintype "input"))
    )
    (net (code "41") (name "Net-(Q2A-D1)") (class "Default")
      (node (ref "Q2") (pin "3") (pinfunction "D2_3") (pintype "passive"))
      (node (ref "Q2") (pin "6") (pinfunction "D1_6") (pintype "passive"))
      (node (ref "U3") (pin "19") (pinfunction "RESET_N_19") (pintype "input"))
    )
    (net (code "42") (name "Net-(Q2B-G2)") (class "Default")
      (node (ref "NC1") (pin "1") (pinfunction "1_1") (pintype "passive"))
      (node (ref "Q2") (pin "5") (pinfunction "G2_5") (pintype "passive"))
    )
    (net (code "43") (name "Net-(Q3A-D1)") (class "Default")
      (node (ref "Q3") (pin "6") (pinfunction "D1_6") (pintype "passive"))
      (node (ref "R12") (pin "2") (pinfunction "2_2") (pintype "passive"))
    )
    (net (code "44") (name "Net-(Q3B-D2)") (class "Default")
      (node (ref "Q3") (pin "3") (pinfunction "D2_3") (pintype "passive"))
      (node (ref "R11") (pin "2") (pinfunction "2_2") (pintype "passive"))
    )
    (net (code "45") (name "Net-(RGB1-B)") (class "Default")
      (node (ref "R15") (pin "2") (pinfunction "2_2") (pintype "passive"))
      (node (ref "RGB1") (pin "3") (pinfunction "B_3") (pintype "passive"))
    )
    (net (code "46") (name "Net-(RGB1-G)") (class "Default")
      (node (ref "R14") (pin "2") (pinfunction "2_2") (pintype "passive"))
      (node (ref "RGB1") (pin "2") (pinfunction "G_2") (pintype "passive"))
    )
    (net (code "47") (name "Net-(RGB1-R)") (class "Default")
      (node (ref "R13") (pin "2") (pinfunction "2_2") (pintype "passive"))
      (node (ref "RGB1") (pin "1") (pinfunction "R_1") (pintype "passive"))
    )
    (net (code "48") (name "Net-(U3-BLUE{slash}RMII_TXEN)") (class "Default")
      (node (ref "R15") (pin "1") (pinfunction "1_1") (pintype "passive"))
      (node (ref "U3") (pin "8") (pinfunction "BLUE/RMII_TXEN_8") (pintype "output"))
    )
    (net (code "49") (name "Net-(U3-RED)") (class "Default")
      (node (ref "R13") (pin "1") (pinfunction "1_1") (pintype "passive"))
      (node (ref "U3") (pin "1") (pinfunction "RED_1") (pintype "output"))
    )
    (net (code "50") (name "Net-(U3-RMII_CLK)") (class "Default")
      (node (ref "TP9") (pin "1") (pintype "passive"))
      (node (ref "U3") (pin "27") (pinfunction "RMII_CLK_27") (pintype "input"))
    )
    (net (code "51") (name "Net-(U3-VCC)") (class "Default")
      (node (ref "C16") (pin "1") (pinfunction "1_1") (pintype "passive"))
      (node (ref "C17") (pin "2") (pinfunction "2_2") (pintype "passive"))
      (node (ref "C28") (pin "1") (pinfunction "1_1") (pintype "passive"))
      (node (ref "J2") (pin "2") (pinfunction "2_2") (pintype "passive"))
      (node (ref "NC5") (pin "1") (pinfunction "1_1") (pintype "passive"))
      (node (ref "U3") (pin "10") (pinfunction "VCC_10") (pintype "power_in"))
      (node (ref "U3") (pin "9") (pinfunction "VCC_IO_9") (pintype "power_in"))
    )
    (net (code "52") (name "Net-(U34-FLAGB)") (class "Default")
      (node (ref "R33") (pin "2") (pinfunction "2_2") (pintype "passive"))
      (node (ref "U34") (pin "4") (pinfunction "FLAGB_4") (pintype "output"))
    )
    (net (code "53") (name "VCC_NINA") (class "Default")
      (node (ref "C35") (pin "1") (pinfunction "1_1") (pintype "passive"))
      (node (ref "C59") (pin "1") (pinfunction "1_1") (pintype "passive"))
      (node (ref "C60") (pin "1") (pinfunction "1_1") (pintype "passive"))
      (node (ref "C64") (pin "1") (pinfunction "1_1") (pintype "passive"))
      (node (ref "C67") (pin "1") (pinfunction "1_1") (pintype "passive"))
      (node (ref "C95") (pin "1") (pinfunction "1_1") (pintype "passive"))
      (node (ref "J2") (pin "3") (pinfunction "3_3") (pintype "passive"))
      (node (ref "NC3") (pin "1") (pinfunction "1_1") (pintype "passive"))
      (node (ref "NC5") (pin "2") (pinfunction "2_2") (pintype "passive"))
      (node (ref "Q3") (pin "1") (pinfunction "S1_1") (pintype "passive"))
      (node (ref "Q3") (pin "4") (pinfunction "S2_4") (pintype "passive"))
      (node (ref "R10") (pin "2") (pinfunction "2_2") (pintype "passive"))
      (node (ref "R33") (pin "1") (pinfunction "1_1") (pintype "passive"))
      (node (ref "R48") (pin "1") (pinfunction "1_1") (pintype "passive"))
      (node (ref "R51") (pin "1") (pinfunction "1_1") (pintype "passive"))
      (node (ref "R52") (pin "1") (pinfunction "1_1") (pintype "passive"))
      (node (ref "RGB1") (pin "4") (pinfunction "A_4") (pintype "passive"))
      (node (ref "TP12") (pin "1") (pintype "passive"))
      (node (ref "U12") (pin "1") (pinfunction "VCCA_1") (pintype "power_in"))
      (node (ref "U12") (pin "10") (pinfunction "DIR3_10") (pintype "input"))
      (node (ref "U12") (pin "2") (pinfunction "DIR1_2") (pintype "input"))
      (node (ref "U14") (pin "1") (pinfunction "VCC(A)_1") (pintype "power_in"))
      (node (ref "U15") (pin "1") (pinfunction "VCCA_1") (pintype "power_in"))
      (node (ref "U15") (pin "15") (pinfunction "DIR2_15") (pintype "input"))
      (node (ref "U15") (pin "7") (pinfunction "DIR4_7") (pintype "input"))
      (node (ref "U16") (pin "1") (pinfunction "VCC(A)_1") (pintype "power_in"))
      (node (ref "U34") (pin "5") (pinfunction "VOUT_5") (pintype "power_in"))
    )
    (net (code "54") (name "VDD_NORA") (class "Default")
      (node (ref "C68") (pin "2") (pinfunction "2_2") (pintype "passive"))
      (node (ref "R63") (pin "1") (pinfunction "1_1") (pintype "passive"))
      (node (ref "U16") (pin "8") (pinfunction "VCC(B)_8") (pintype "power_in"))
    )
    (net (code "55") (name "unconnected-(U3-ANT-Pad13)") (class "Default")
      (node (ref "U3") (pin "13") (pinfunction "ANT_13") (pintype "bidirectional+no_connect"))
    )
    (net (code "56") (name "unconnected-(U3-LOG_BOOT-Pad32)") (class "Default")
      (node (ref "U3") (pin "32") (pinfunction "LOG_BOOT_32") (pintype "input+no_connect"))
    )
    (net (code "57") (name "unconnected-(U3-LPO_IN-Pad5)") (class "Default")
      (node (ref "U3") (pin "5") (pinfunction "LPO_IN_5") (pintype "input+no_connect"))
    )
    (net (code "58") (name "unconnected-(U3-RMII_MDCLK-Pad25)") (class "Default")
      (node (ref "U3") (pin "25") (pinfunction "RMII_MDCLK_25") (pintype "output+no_connect"))
    )
    (net (code "59") (name "unconnected-(U3-RMII_MDIO-Pad24)") (class "Default")
      (node (ref "U3") (pin "24") (pinfunction "RMII_MDIO_24") (pintype "bidirectional+no_connect"))
    )
    (net (code "60") (name "unconnected-(U3-RSVD2-Pad2)") (class "Default")
      (node (ref "U3") (pin "2") (pinfunction "RSVD2_2") (pintype "passive+no_connect"))
    )
    (net (code "61") (name "unconnected-(U3-RSVD3-Pad3)") (class "Default")
      (node (ref "U3") (pin "3") (pinfunction "RSVD3_3") (pintype "passive+no_connect"))
    )
    (net (code "62") (name "unconnected-(U3-RSVD4-Pad4)") (class "Default")
      (node (ref "U3") (pin "4") (pinfunction "RSVD4_4") (pintype "passive+no_connect"))
    )
    (net (code "63") (name "unconnected-(U3-RSVD11-Pad11)") (class "Default")
      (node (ref "U3") (pin "11") (pinfunction "RSVD11_11") (pintype "passive+no_connect"))
    )
    (net (code "64") (name "unconnected-(U3-RSVD15-Pad15)") (class "Default")
      (node (ref "U3") (pin "15") (pinfunction "RSVD15_15") (pintype "passive+no_connect"))
    )
    (net (code "65") (name "unconnected-(U3-RSVD28-Pad28)") (class "Default")
      (node (ref "U3") (pin "28") (pinfunction "RSVD28_28") (pintype "passive+no_connect"))
    )
    (net (code "66") (name "unconnected-(U3-RSVD29-Pad29)") (class "Default")
      (node (ref "U3") (pin "29") (pinfunction "RSVD29_29") (pintype "passive+no_connect"))
    )
    (net (code "67") (name "unconnected-(U3-RSVD31-Pad31)") (class "Default")
      (node (ref "U3") (pin "31") (pinfunction "RSVD31_31") (pintype "passive+no_connect"))
    )
    (net (code "68") (name "unconnected-(U3-RSVD33-Pad33)") (class "Default")
      (node (ref "U3") (pin "33") (pinfunction "RSVD33_33") (pintype "passive+no_connect"))
    )
    (net (code "69") (name "unconnected-(U3-RSVD34-Pad34)") (class "Default")
      (node (ref "U3") (pin "34") (pinfunction "RSVD34_34") (pintype "passive+no_connect"))
    )
    (net (code "70") (name "unconnected-(U3-RSVD35-Pad35)") (class "Default")
      (node (ref "U3") (pin "35") (pinfunction "RSVD35_35") (pintype "passive+no_connect"))
    )
    (net (code "71") (name "unconnected-(U3-RSVD36-Pad36)") (class "Default")
      (node (ref "U3") (pin "36") (pinfunction "RSVD36_36") (pintype "passive+no_connect"))
    )
  )
)
